# Alcohol_Detectie.net
KiCad netlist of a schematic drawn in Altium Designer
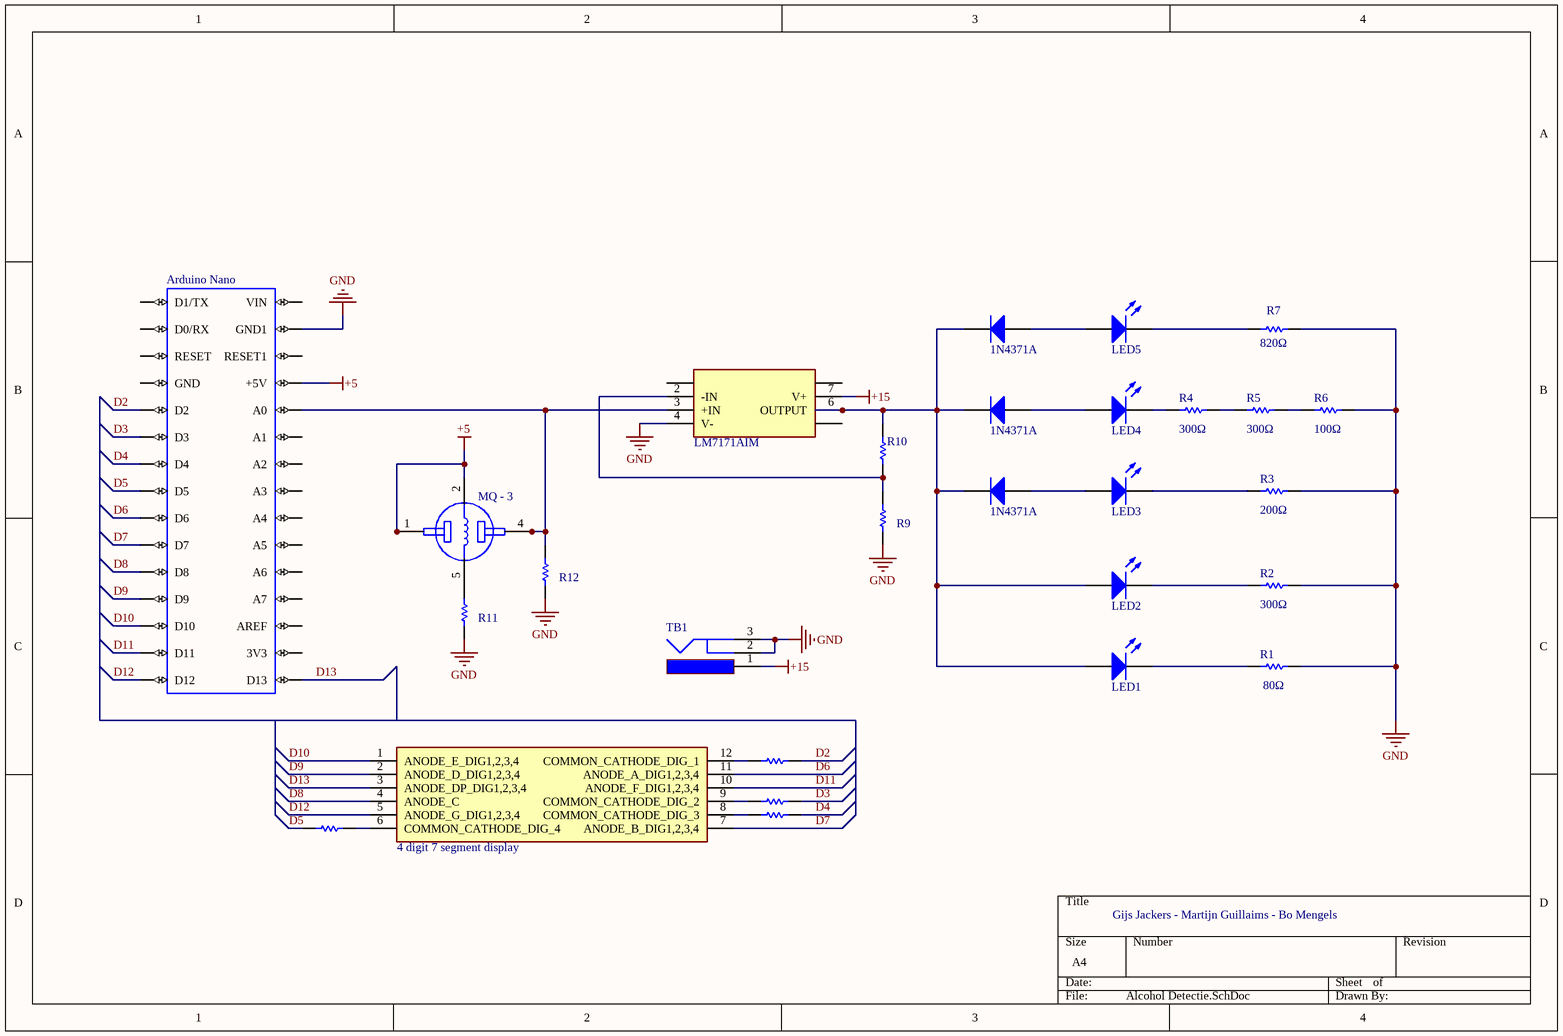
[diagram p0: Alcohol Detectie.SchDoc]

(export (version "E")
  (design (tool "Eeschema 10.0.6"))
  (components
    (comp (ref "4 digit 7 segment display")
      (value "CC56-12SRWA")
      (footprint "SamacSys:CC5612SRWA")
      (description "Display")
      (fields (field (name "MOUSER2 PART NUMBER") "604-CC56-12SRWA"))
      (libsource (lib "*") (part "CC56-12SRWA"))
    )
    (comp (ref "Arduino Nano")
      (value "ARDUINONANO")
      (footprint "PDIP-32")
      (description "Arduino; 20MHz; 3.3Ã·5VDC; Flash: 32kB; SRAM: 2kB; ATMEGA328,FT232R")
      (fields (field (name "MF") "Arduino"))
      (libsource (lib "ARDUINONANO") (part "ARDUINONANO"))
    )
    (comp (ref "COMPERATOR")
      (value "LM7171AIM")
      (footprint "SamacSys:SOIC127P600X175-8N")
      (description "Integrated Circuit")
      (fields
        (field (name "MOUSER2 PART NUMBER") "926-LM7171AIMX/NOPB")
        (field (name "MANUFACTURER_PART_NUMBER") "LM7171AIMX/NOPB")
      )
      (libsource (lib "*") (part "LM7171AIMX_NOPB"))
    )
    (comp (ref "D1")
      (value "1N4371A")
      (footprint "DO-35")
      (description "High Conductance Fast Diode")
      (fields (field (name "PUBLISHER") "Altium Limited"))
      (libsource (lib "Miscellaneous Devices") (part "Diode 1N4148"))
    )
    (comp (ref "D2")
      (value "1N4371A")
      (footprint "DO-35")
      (description "High Conductance Fast Diode")
      (fields (field (name "PUBLISHER") "Altium Limited"))
      (libsource (lib "Miscellaneous Devices") (part "Diode 1N4148"))
    )
    (comp (ref "D3")
      (value "1N4371A")
      (footprint "DO-35")
      (description "High Conductance Fast Diode")
      (fields (field (name "PUBLISHER") "Altium Limited"))
      (libsource (lib "Miscellaneous Devices") (part "Diode 1N4148"))
    )
    (comp (ref "GROEN")
      (value "LED1")
      (footprint "LED-1")
      (description "Typical RED GaAs LED")
      (fields (field (name "PUBLISHER") "Altium Limited"))
      (libsource (lib "Miscellaneous Devices") (part "LED1"))
    )
    (comp (ref "MQ - 3")
      (value "SEN-08880")
      (footprint "XDCR_SEN-08880")
      (description "Alcohol _C2H6O_ Sensor 0 V ~ 3.3 V")
      (fields (field (name "MF") "SparkFun Electronics"))
      (libsource (lib "SEN-08880") (part "SEN-08880"))
    )
    (comp (ref "ORANJE_1")
      (value "LED2")
      (footprint "LED-1")
      (description "Typical RED GaAs LED")
      (fields (field (name "PUBLISHER") "Altium Limited"))
      (libsource (lib "Miscellaneous Devices") (part "LED1"))
    )
    (comp (ref "ORANJE_2")
      (value "LED3")
      (footprint "LED-1")
      (description "Typical RED GaAs LED")
      (fields (field (name "PUBLISHER") "Altium Limited"))
      (libsource (lib "Miscellaneous Devices") (part "LED1"))
    )
    (comp (ref "R1")
      (value "80Ω")
      (footprint "RESC2013X50X30LL20T20")
      (fields (field (name "MANUFACTURER") "Vishay Dale") (field (name "PART NUMBER") "CRCW08050000Z0EA"))
      (libsource (lib "Altium Content Vault") (part "RES"))
    )
    (comp (ref "R2")
      (value "300Ω")
      (footprint "RESC2013X50X30LL20T20")
      (fields (field (name "MANUFACTURER") "Vishay Dale") (field (name "PART NUMBER") "CRCW08050000Z0EA"))
      (libsource (lib "Altium Content Vault") (part "RES"))
    )
    (comp (ref "R3")
      (value "200Ω")
      (footprint "RESC2013X50X30LL20T20")
      (fields (field (name "MANUFACTURER") "Vishay Dale") (field (name "PART NUMBER") "CRCW08050000Z0EA"))
      (libsource (lib "Altium Content Vault") (part "RES"))
    )
    (comp (ref "R4")
      (value "300Ω")
      (footprint "RESC2013X50X30LL20T20")
      (fields (field (name "MANUFACTURER") "Vishay Dale") (field (name "PART NUMBER") "CRCW08050000Z0EA"))
      (libsource (lib "Altium Content Vault") (part "RES"))
    )
    (comp (ref "R5")
      (value "300Ω")
      (footprint "RESC2013X50X30LL20T20")
      (fields (field (name "MANUFACTURER") "Vishay Dale") (field (name "PART NUMBER") "CRCW08050000Z0EA"))
      (libsource (lib "Altium Content Vault") (part "RES"))
    )
    (comp (ref "R6")
      (value "100Ω")
      (footprint "RESC2013X50X30LL20T20")
      (fields (field (name "MANUFACTURER") "Vishay Dale") (field (name "PART NUMBER") "CRCW08050000Z0EA"))
      (libsource (lib "Altium Content Vault") (part "RES"))
    )
    (comp (ref "R7")
      (value "820Ω")
      (footprint "RESC2013X50X30LL20T20")
      (fields (field (name "MANUFACTURER") "Vishay Dale") (field (name "PART NUMBER") "CRCW08050000Z0EA"))
      (libsource (lib "Altium Content Vault") (part "RES"))
    )
    (comp (ref "R9")
      (value "1k Ω")
      (footprint "RESC2013X50X30LL20T20")
      (fields (field (name "MANUFACTURER") "Vishay Dale") (field (name "PART NUMBER") "CRCW08050000Z0EA"))
      (libsource (lib "Altium Content Vault") (part "RES"))
    )
    (comp (ref "R10")
      (value "1k Ω")
      (footprint "RESC2013X50X30LL20T20")
      (fields (field (name "MANUFACTURER") "Vishay Dale") (field (name "PART NUMBER") "CRCW08050000Z0EA"))
      (libsource (lib "Altium Content Vault") (part "RES"))
    )
    (comp (ref "R11")
      (value "5,1 Ω")
      (footprint "RESC2013X50X30LL20T20")
      (fields (field (name "MANUFACTURER") "Vishay Dale") (field (name "PART NUMBER") "CRCW08050000Z0EA"))
      (libsource (lib "Altium Content Vault") (part "RES"))
    )
    (comp (ref "R12")
      (value "1k Ω")
      (footprint "RESC2013X50X30LL20T20")
      (fields (field (name "MANUFACTURER") "Vishay Dale") (field (name "PART NUMBER") "CRCW08050000Z0EA"))
      (libsource (lib "Altium Content Vault") (part "RES"))
    )
    (comp (ref "R13")
      (value "330 Ω")
      (footprint "RESC2013X50X30LL20T20")
      (fields (field (name "MANUFACTURER") "Vishay Dale") (field (name "PART NUMBER") "CRCW08050000Z0EA"))
      (libsource (lib "Altium Content Vault") (part "RES"))
    )
    (comp (ref "R14")
      (value "330 Ω")
      (footprint "RESC2013X50X30LL20T20")
      (fields (field (name "MANUFACTURER") "Vishay Dale") (field (name "PART NUMBER") "CRCW08050000Z0EA"))
      (libsource (lib "Altium Content Vault") (part "RES"))
    )
    (comp (ref "R15")
      (value "330 Ω")
      (footprint "RESC2013X50X30LL20T20")
      (fields (field (name "MANUFACTURER") "Vishay Dale") (field (name "PART NUMBER") "CRCW08050000Z0EA"))
      (libsource (lib "Altium Content Vault") (part "RES"))
    )
    (comp (ref "R16")
      (value "330 Ω")
      (footprint "RESC2013X50X30LL20T20")
      (fields (field (name "MANUFACTURER") "Vishay Dale") (field (name "PART NUMBER") "CRCW08050000Z0EA"))
      (libsource (lib "Altium Content Vault") (part "RES"))
    )
    (comp (ref "ROOD_1")
      (value "LED4")
      (footprint "LED-1")
      (description "Typical RED GaAs LED")
      (fields (field (name "PUBLISHER") "Altium Limited"))
      (libsource (lib "Miscellaneous Devices") (part "LED1"))
    )
    (comp (ref "ROOD_2")
      (value "LED5")
      (footprint "LED-1")
      (description "Typical RED GaAs LED")
      (fields (field (name "PUBLISHER") "Altium Limited"))
      (libsource (lib "Miscellaneous Devices") (part "LED1"))
    )
    (comp (ref "TB1")
      (value "Component_1")
      (footprint "MJ-180PH")
      (libsource (lib "TB1") (part "Component_1"))
    )
  )
  (nets
    (net (code "1") (name "+5") (class "Default")
      (node (ref "Arduino Nano") (pin "+5V") (pinfunction "+5V_+5V") (pintype "bidirectional"))
      (node (ref "MQ - 3") (pin "1") (pinfunction "A_1") (pintype "passive"))
      (node (ref "MQ - 3") (pin "2") (pinfunction "H1_2") (pintype "passive"))
      (node (ref "MQ - 3") (pin "3") (pinfunction "A_3") (pintype "passive"))
    )
    (net (code "2") (name "+15") (class "Default")
      (node (ref "COMPERATOR") (pin "7") (pinfunction "V+_7") (pintype "passive"))
      (node (ref "TB1") (pin "1") (pinfunction "1_1") (pintype "passive"))
    )
    (net (code "3") (name "/D2") (class "Default")
      (node (ref "Arduino Nano") (pin "D2") (pinfunction "D2_D2") (pintype "bidirectional"))
      (node (ref "R14") (pin "1") (pinfunction "1_1") (pintype "passive"))
    )
    (net (code "4") (name "/D3") (class "Default")
      (node (ref "Arduino Nano") (pin "D3") (pinfunction "D3_D3") (pintype "bidirectional"))
      (node (ref "R15") (pin "1") (pinfunction "1_1") (pintype "passive"))
    )
    (net (code "5") (name "/D4") (class "Default")
      (node (ref "Arduino Nano") (pin "D4") (pinfunction "D4_D4") (pintype "bidirectional"))
      (node (ref "R16") (pin "1") (pinfunction "1_1") (pintype "passive"))
    )
    (net (code "6") (name "/D5") (class "Default")
      (node (ref "Arduino Nano") (pin "D5") (pinfunction "D5_D5") (pintype "bidirectional"))
      (node (ref "R13") (pin "2") (pinfunction "2_2") (pintype "passive"))
    )
    (net (code "7") (name "/D6") (class "Default")
      (node (ref "4 digit 7 segment display") (pin "11") (pinfunction "ANODE_A_DIG1,2,3,4_11") (pintype "passive"))
      (node (ref "Arduino Nano") (pin "D6") (pinfunction "D6_D6") (pintype "bidirectional"))
    )
    (net (code "8") (name "/D7") (class "Default")
      (node (ref "4 digit 7 segment display") (pin "7") (pinfunction "ANODE_B_DIG1,2,3,4_7") (pintype "passive"))
      (node (ref "Arduino Nano") (pin "D7") (pinfunction "D7_D7") (pintype "bidirectional"))
    )
    (net (code "9") (name "/D8") (class "Default")
      (node (ref "4 digit 7 segment display") (pin "4") (pinfunction "ANODE_C_4") (pintype "passive"))
      (node (ref "Arduino Nano") (pin "D8") (pinfunction "D8_D8") (pintype "bidirectional"))
    )
    (net (code "10") (name "/D9") (class "Default")
      (node (ref "4 digit 7 segment display") (pin "2") (pinfunction "ANODE_D_DIG1,2,3,4_2") (pintype "passive"))
      (node (ref "Arduino Nano") (pin "D9") (pinfunction "D9_D9") (pintype "bidirectional"))
    )
    (net (code "11") (name "/D10") (class "Default")
      (node (ref "4 digit 7 segment display") (pin "1") (pinfunction "ANODE_E_DIG1,2,3,4_1") (pintype "passive"))
      (node (ref "Arduino Nano") (pin "D10") (pinfunction "D10_D10") (pintype "bidirectional"))
    )
    (net (code "12") (name "/D11") (class "Default")
      (node (ref "4 digit 7 segment display") (pin "10") (pinfunction "ANODE_F_DIG1,2,3,4_10") (pintype "passive"))
      (node (ref "Arduino Nano") (pin "D11") (pinfunction "D11_D11") (pintype "bidirectional"))
    )
    (net (code "13") (name "/D12") (class "Default")
      (node (ref "4 digit 7 segment display") (pin "5") (pinfunction "ANODE_G_DIG1,2,3,4_5") (pintype "passive"))
      (node (ref "Arduino Nano") (pin "D12") (pinfunction "D12_D12") (pintype "bidirectional"))
    )
    (net (code "14") (name "/D13") (class "Default")
      (node (ref "4 digit 7 segment display") (pin "3") (pinfunction "ANODE_DP_DIG1,2,3,4_3") (pintype "passive"))
      (node (ref "Arduino Nano") (pin "D13") (pinfunction "D13_D13") (pintype "bidirectional"))
    )
    (net (code "15") (name "GND") (class "Default")
      (node (ref "Arduino Nano") (pin "GND1") (pinfunction "GND1_GND1") (pintype "bidirectional"))
      (node (ref "COMPERATOR") (pin "4") (pinfunction "V-_4") (pintype "passive"))
      (node (ref "R1") (pin "2") (pinfunction "2_2") (pintype "passive"))
      (node (ref "R11") (pin "1") (pinfunction "1_1") (pintype "passive"))
      (node (ref "R12") (pin "1") (pinfunction "1_1") (pintype "passive"))
      (node (ref "R2") (pin "2") (pinfunction "2_2") (pintype "passive"))
      (node (ref "R3") (pin "2") (pinfunction "2_2") (pintype "passive"))
      (node (ref "R6") (pin "2") (pinfunction "2_2") (pintype "passive"))
      (node (ref "R7") (pin "2") (pinfunction "2_2") (pintype "passive"))
      (node (ref "R9") (pin "1") (pinfunction "1_1") (pintype "passive"))
      (node (ref "TB1") (pin "2") (pinfunction "2_2") (pintype "passive"))
      (node (ref "TB1") (pin "3") (pinfunction "3_3") (pintype "passive"))
    )
    (net (code "16") (name "Net-(4 digit 7 segment display-COMMON_CATHODE_DIG_1)") (class "Default")
      (node (ref "4 digit 7 segment display") (pin "12") (pinfunction "COMMON_CATHODE_DIG_1_12") (pintype "passive"))
      (node (ref "R14") (pin "2") (pinfunction "2_2") (pintype "passive"))
    )
    (net (code "17") (name "Net-(4 digit 7 segment display-COMMON_CATHODE_DIG_2)") (class "Default")
      (node (ref "4 digit 7 segment display") (pin "9") (pinfunction "COMMON_CATHODE_DIG_2_9") (pintype "passive"))
      (node (ref "R15") (pin "2") (pinfunction "2_2") (pintype "passive"))
    )
    (net (code "18") (name "Net-(4 digit 7 segment display-COMMON_CATHODE_DIG_3)") (class "Default")
      (node (ref "4 digit 7 segment display") (pin "8") (pinfunction "COMMON_CATHODE_DIG_3_8") (pintype "passive"))
      (node (ref "R16") (pin "2") (pinfunction "2_2") (pintype "passive"))
    )
    (net (code "19") (name "Net-(4 digit 7 segment display-COMMON_CATHODE_DIG_4)") (class "Default")
      (node (ref "4 digit 7 segment display") (pin "6") (pinfunction "COMMON_CATHODE_DIG_4_6") (pintype "passive"))
      (node (ref "R13") (pin "1") (pinfunction "1_1") (pintype "passive"))
    )
    (net (code "20") (name "Net-(COMPERATOR-+IN)") (class "Default")
      (node (ref "Arduino Nano") (pin "A0") (pinfunction "A0_A0") (pintype "bidirectional"))
      (node (ref "COMPERATOR") (pin "3") (pinfunction "+IN_3") (pintype "passive"))
      (node (ref "MQ - 3") (pin "4") (pinfunction "B_4") (pintype "passive"))
      (node (ref "MQ - 3") (pin "6") (pinfunction "B_6") (pintype "passive"))
      (node (ref "R12") (pin "2") (pinfunction "2_2") (pintype "passive"))
    )
    (net (code "21") (name "Net-(COMPERATOR--IN)") (class "Default")
      (node (ref "COMPERATOR") (pin "2") (pinfunction "-IN_2") (pintype "passive"))
      (node (ref "R10") (pin "1") (pinfunction "1_1") (pintype "passive"))
      (node (ref "R9") (pin "2") (pinfunction "2_2") (pintype "passive"))
    )
    (net (code "22") (name "Net-(COMPERATOR-OUTPUT)") (class "Default")
      (node (ref "COMPERATOR") (pin "6") (pinfunction "OUTPUT_6") (pintype "passive"))
      (node (ref "D1") (pin "2") (pinfunction "K_2") (pintype "passive"))
      (node (ref "D2") (pin "2") (pinfunction "K_2") (pintype "passive"))
      (node (ref "D3") (pin "2") (pinfunction "K_2") (pintype "passive"))
      (node (ref "GROEN") (pin "1") (pinfunction "A_1") (pintype "passive"))
      (node (ref "ORANJE_1") (pin "1") (pinfunction "A_1") (pintype "passive"))
      (node (ref "R10") (pin "2") (pinfunction "2_2") (pintype "passive"))
    )
    (net (code "23") (name "Net-(D1-A)") (class "Default")
      (node (ref "D1") (pin "1") (pinfunction "A_1") (pintype "passive"))
      (node (ref "ORANJE_2") (pin "1") (pinfunction "A_1") (pintype "passive"))
    )
    (net (code "24") (name "Net-(D2-A)") (class "Default")
      (node (ref "D2") (pin "1") (pinfunction "A_1") (pintype "passive"))
      (node (ref "ROOD_1") (pin "1") (pinfunction "A_1") (pintype "passive"))
    )
    (net (code "25") (name "Net-(D3-A)") (class "Default")
      (node (ref "D3") (pin "1") (pinfunction "A_1") (pintype "passive"))
      (node (ref "ROOD_2") (pin "1") (pinfunction "A_1") (pintype "passive"))
    )
    (net (code "26") (name "Net-(GROEN-K)") (class "Default")
      (node (ref "GROEN") (pin "2") (pinfunction "K_2") (pintype "passive"))
      (node (ref "R1") (pin "1") (pinfunction "1_1") (pintype "passive"))
    )
    (net (code "27") (name "Net-(MQ - 3-H2)") (class "Default")
      (node (ref "MQ - 3") (pin "5") (pinfunction "H2_5") (pintype "passive"))
      (node (ref "R11") (pin "2") (pinfunction "2_2") (pintype "passive"))
    )
    (net (code "28") (name "Net-(ORANJE_1-K)") (class "Default")
      (node (ref "ORANJE_1") (pin "2") (pinfunction "K_2") (pintype "passive"))
      (node (ref "R2") (pin "1") (pinfunction "1_1") (pintype "passive"))
    )
    (net (code "29") (name "Net-(ORANJE_2-K)") (class "Default")
      (node (ref "ORANJE_2") (pin "2") (pinfunction "K_2") (pintype "passive"))
      (node (ref "R3") (pin "1") (pinfunction "1_1") (pintype "passive"))
    )
    (net (code "30") (name "Net-(R4-Pad2)") (class "Default")
      (node (ref "R4") (pin "2") (pinfunction "2_2") (pintype "passive"))
      (node (ref "R5") (pin "1") (pinfunction "1_1") (pintype "passive"))
    )
    (net (code "31") (name "Net-(R5-Pad2)") (class "Default")
      (node (ref "R5") (pin "2") (pinfunction "2_2") (pintype "passive"))
      (node (ref "R6") (pin "1") (pinfunction "1_1") (pintype "passive"))
    )
    (net (code "32") (name "Net-(ROOD_1-K)") (class "Default")
      (node (ref "R4") (pin "1") (pinfunction "1_1") (pintype "passive"))
      (node (ref "ROOD_1") (pin "2") (pinfunction "K_2") (pintype "passive"))
    )
    (net (code "33") (name "Net-(ROOD_2-K)") (class "Default")
      (node (ref "R7") (pin "1") (pinfunction "1_1") (pintype "passive"))
      (node (ref "ROOD_2") (pin "2") (pinfunction "K_2") (pintype "passive"))
    )
    (net (code "34") (name "unconnected-(Arduino Nano-Pad3V3)") (class "Default")
      (node (ref "Arduino Nano") (pin "3V3") (pinfunction "3V3_3V3") (pintype "bidirectional"))
    )
    (net (code "35") (name "unconnected-(Arduino Nano-PadA1)") (class "Default")
      (node (ref "Arduino Nano") (pin "A1") (pinfunction "A1_A1") (pintype "bidirectional"))
    )
    (net (code "36") (name "unconnected-(Arduino Nano-PadA2)") (class "Default")
      (node (ref "Arduino Nano") (pin "A2") (pinfunction "A2_A2") (pintype "bidirectional"))
    )
    (net (code "37") (name "unconnected-(Arduino Nano-PadA3)") (class "Default")
      (node (ref "Arduino Nano") (pin "A3") (pinfunction "A3_A3") (pintype "bidirectional"))
    )
    (net (code "38") (name "unconnected-(Arduino Nano-PadA4)") (class "Default")
      (node (ref "Arduino Nano") (pin "A4") (pinfunction "A4_A4") (pintype "bidirectional"))
    )
    (net (code "39") (name "unconnected-(Arduino Nano-PadA5)") (class "Default")
      (node (ref "Arduino Nano") (pin "A5") (pinfunction "A5_A5") (pintype "bidirectional"))
    )
    (net (code "40") (name "unconnected-(Arduino Nano-PadA6)") (class "Default")
      (node (ref "Arduino Nano") (pin "A6") (pinfunction "A6_A6") (pintype "bidirectional"))
    )
    (net (code "41") (name "unconnected-(Arduino Nano-PadA7)") (class "Default")
      (node (ref "Arduino Nano") (pin "A7") (pinfunction "A7_A7") (pintype "bidirectional"))
    )
    (net (code "42") (name "unconnected-(Arduino Nano-PadAREF)") (class "Default")
      (node (ref "Arduino Nano") (pin "AREF") (pinfunction "AREF_AREF") (pintype "bidirectional"))
    )
    (net (code "43") (name "unconnected-(Arduino Nano-PadD0{slash}RX)") (class "Default")
      (node (ref "Arduino Nano") (pin "D0/RX") (pinfunction "D0/RX_D0/RX") (pintype "bidirectional"))
    )
    (net (code "44") (name "unconnected-(Arduino Nano-PadD1{slash}TX)") (class "Default")
      (node (ref "Arduino Nano") (pin "D1/TX") (pinfunction "D1/TX_D1/TX") (pintype "bidirectional"))
    )
    (net (code "45") (name "unconnected-(Arduino Nano-PadGND)") (class "Default")
      (node (ref "Arduino Nano") (pin "GND") (pinfunction "GND_GND") (pintype "bidirectional"))
    )
    (net (code "46") (name "unconnected-(Arduino Nano-PadRESET)") (class "Default")
      (node (ref "Arduino Nano") (pin "RESET") (pinfunction "RESET_RESET") (pintype "bidirectional"))
    )
    (net (code "47") (name "unconnected-(Arduino Nano-PadRESET1)") (class "Default")
      (node (ref "Arduino Nano") (pin "RESET1") (pinfunction "RESET1_RESET1") (pintype "bidirectional"))
    )
    (net (code "48") (name "unconnected-(Arduino Nano-PadVIN)") (class "Default")
      (node (ref "Arduino Nano") (pin "VIN") (pinfunction "VIN_VIN") (pintype "bidirectional"))
    )
    (net (code "49") (name "unconnected-(COMPERATOR-N{slash}C_1-Pad1)") (class "Default")
      (node (ref "COMPERATOR") (pin "1") (pinfunction "N/C_1_1") (pintype "passive"))
    )
    (net (code "50") (name "unconnected-(COMPERATOR-N{slash}C_2-Pad5)") (class "Default")
      (node (ref "COMPERATOR") (pin "5") (pinfunction "N/C_2_5") (pintype "passive"))
    )
    (net (code "51") (name "unconnected-(COMPERATOR-N{slash}C_3-Pad8)") (class "Default")
      (node (ref "COMPERATOR") (pin "8") (pinfunction "N/C_3_8") (pintype "passive"))
    )
  )
)
